# sheet1.net
KiCad netlist of a schematic drawn in Altium Designer
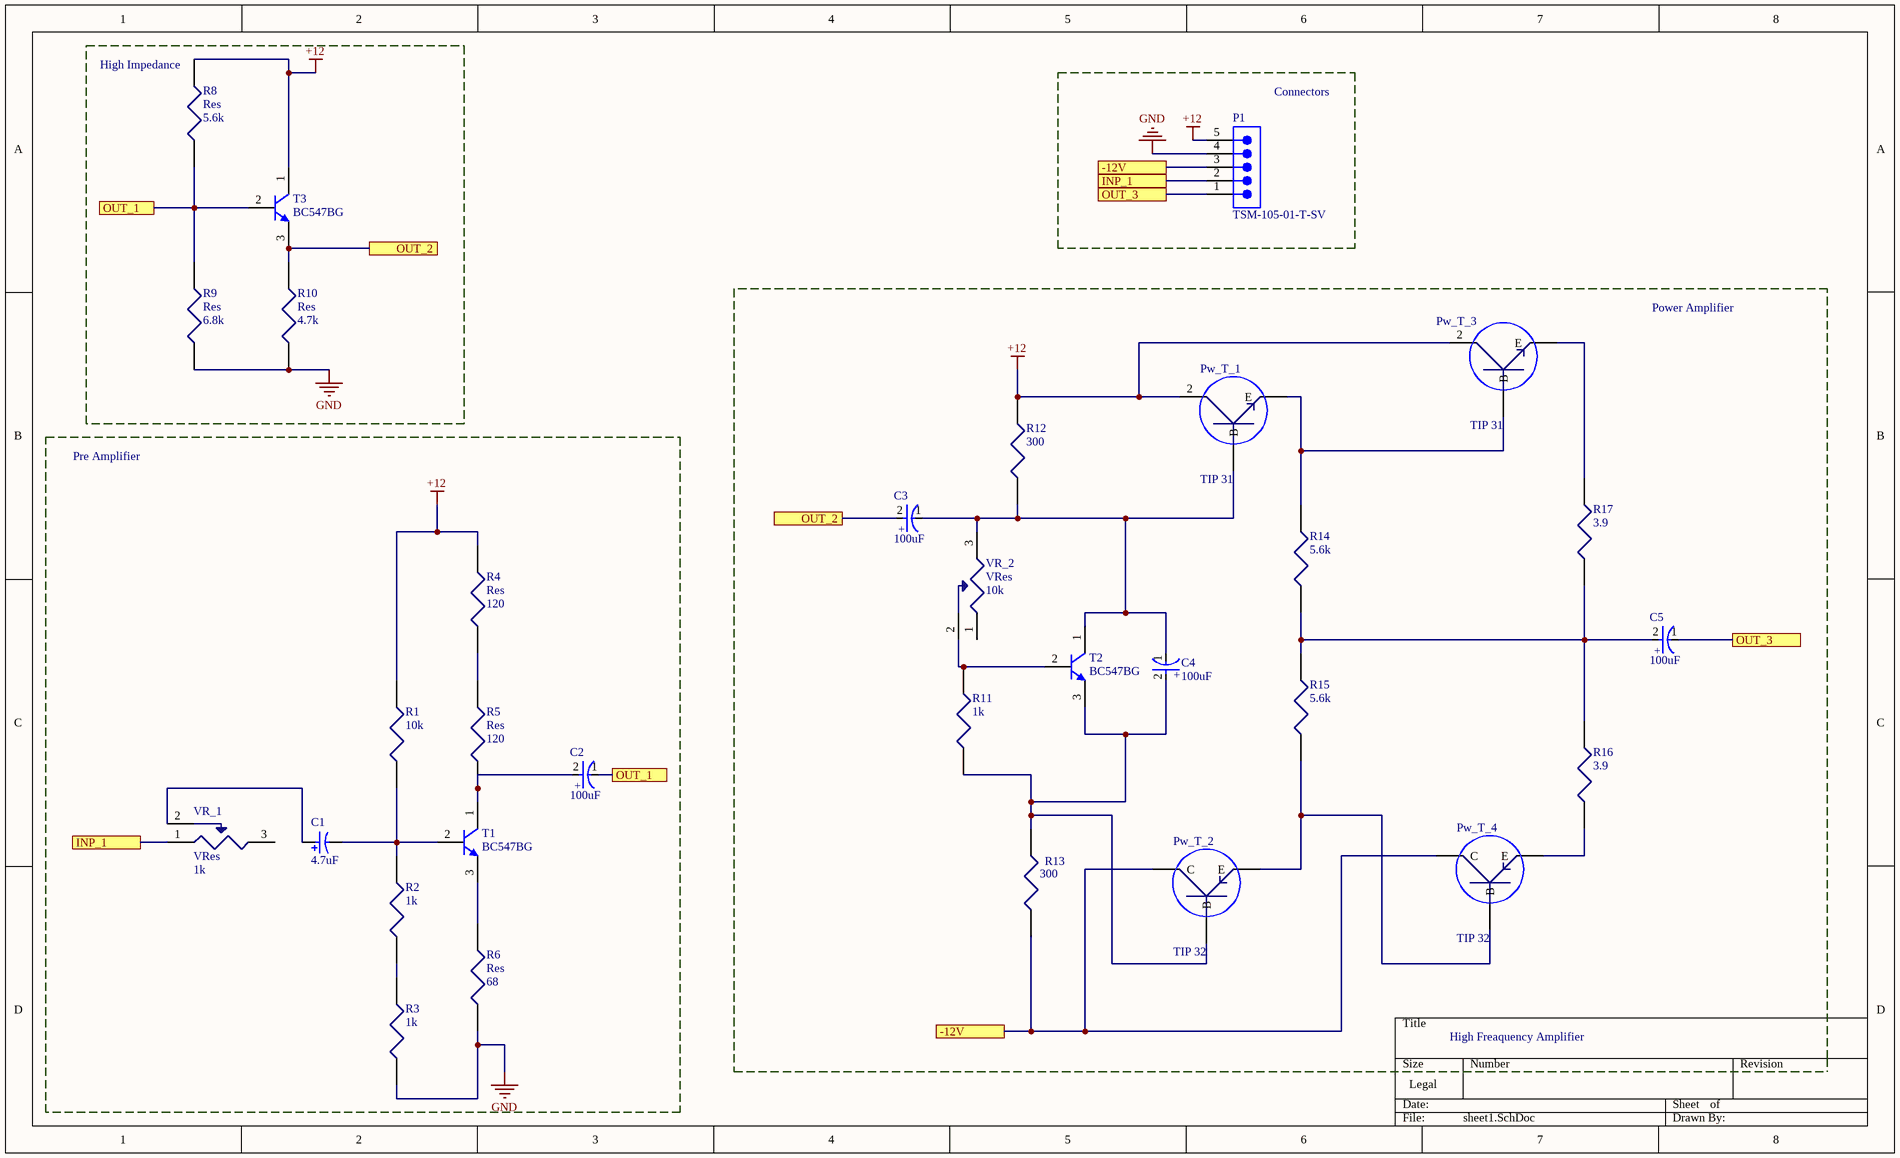
[diagram p0: sheet1.SchDoc]

(export (version "E")
  (design (tool "Eeschema 10.0.6"))
  (components
    (comp (ref "C1")
      (value "4.7uF")
      (footprint "CAPPR55-200-1100X500X1200")
      (description "Aluminum Electrolytic Capacitor, 4.7 uF, +/- 20%, 50 V, -40 to 85 degC, 2-Pin THD, RoHS, Bulk")
      (fields (field (name "VOLTAGE") "50V") (field (name "MANUFACTURER") "Panasonic"))
      (libsource (lib "Altium Content Vault") (part "CAP-P-2"))
    )
    (comp (ref "C2")
      (value "100uF")
      (footprint "FP-EEU-FR1H101B-MFG")
      (description "CAP ALUM 100UF 20% 50V RADIAL")
      (fields (field (name "TOLERANCE") "20%"))
      (libsource (lib "Altium Content Vault") (part "cf48714ba7e38822c1575c7ec0b6d1f"))
    )
    (comp (ref "C3")
      (value "100uF")
      (footprint "FP-EEU-FR1H101B-MFG")
      (description "CAP ALUM 100UF 20% 50V RADIAL")
      (fields (field (name "TOLERANCE") "20%"))
      (libsource (lib "Altium Content Vault") (part "cf48714ba7e38822c1575c7ec0b6d1f"))
    )
    (comp (ref "C4")
      (value "100uF")
      (footprint "FP-EEU-FR1H101B-MFG")
      (description "CAP ALUM 100UF 20% 50V RADIAL")
      (fields (field (name "TOLERANCE") "20%"))
      (libsource (lib "Altium Content Vault") (part "cf48714ba7e38822c1575c7ec0b6d1f"))
    )
    (comp (ref "C5")
      (value "100uF")
      (footprint "FP-EEU-FR1H101B-MFG")
      (description "CAP ALUM 100UF 20% 50V RADIAL")
      (fields (field (name "TOLERANCE") "20%"))
      (libsource (lib "Altium Content Vault") (part "cf48714ba7e38822c1575c7ec0b6d1f"))
    )
    (comp (ref "P1")
      (value "TSM-105-01-T-SV")
      (footprint "SMTC-TSM-105-01-X-SV")
      (description "0.025\" SQ Post Header, Surface Mount, Vertical, -55 to 105 degC, 2.54 mm Pitch, 5-Pin, Male, RoHS")
      (fields (field (name "MANUFACTURER") "Samtec"))
      (libsource (lib "Altium Content Vault") (part "SMTC-TSM-105-01-X-SV"))
    )
    (comp (ref "Pw_T_1") (value "TIP 31") (footprint "TIP 31") (libsource (lib "Funcgen") (part "TIP 31")))
    (comp (ref "Pw_T_2") (value "TIP 32") (footprint "TIP 31") (libsource (lib "Funcgen") (part "TIP 32")))
    (comp (ref "Pw_T_3") (value "TIP 31") (footprint "TIP 31") (libsource (lib "Funcgen") (part "TIP 31")))
    (comp (ref "Pw_T_4") (value "TIP 32") (footprint "TIP 31") (libsource (lib "Funcgen") (part "TIP 32")))
    (comp (ref "R1") (value "10k") (footprint "Res") (libsource (lib "Funcgen") (part "Res")))
    (comp (ref "R2") (value "1k") (footprint "Res") (libsource (lib "Funcgen") (part "Res")))
    (comp (ref "R3") (value "1k") (footprint "Res") (libsource (lib "Funcgen") (part "Res")))
    (comp (ref "R4")
      (value "Res")
      (footprint "Res")
      (fields (field (name "ALTIUM_VALUE") "120"))
      (libsource (lib "Funcgen") (part "Res"))
    )
    (comp (ref "R5")
      (value "Res")
      (footprint "Res")
      (fields (field (name "ALTIUM_VALUE") "120"))
      (libsource (lib "Funcgen") (part "Res"))
    )
    (comp (ref "R6")
      (value "Res")
      (footprint "Res")
      (fields (field (name "ALTIUM_VALUE") "68"))
      (libsource (lib "Funcgen") (part "Res"))
    )
    (comp (ref "R8")
      (value "Res")
      (footprint "Res")
      (fields (field (name "ALTIUM_VALUE") "5.6k"))
      (libsource (lib "Funcgen") (part "Res"))
    )
    (comp (ref "R9")
      (value "Res")
      (footprint "Res")
      (fields (field (name "ALTIUM_VALUE") "6.8k"))
      (libsource (lib "Funcgen") (part "Res"))
    )
    (comp (ref "R10")
      (value "Res")
      (footprint "Res")
      (fields (field (name "ALTIUM_VALUE") "4.7k"))
      (libsource (lib "Funcgen") (part "Res"))
    )
    (comp (ref "R11") (value "1k") (footprint "Res") (libsource (lib "Funcgen") (part "Res")))
    (comp (ref "R12") (value "300") (footprint "Res") (libsource (lib "Funcgen") (part "Res")))
    (comp (ref "R13") (value "300") (footprint "Res") (libsource (lib "Funcgen") (part "Res")))
    (comp (ref "R14") (value "5.6k") (footprint "Res") (libsource (lib "Funcgen") (part "Res")))
    (comp (ref "R15") (value "5.6k") (footprint "Res") (libsource (lib "Funcgen") (part "Res")))
    (comp (ref "R16") (value "3.9") (footprint "Res") (libsource (lib "Funcgen") (part "Res")))
    (comp (ref "R17") (value "3.9") (footprint "Res") (libsource (lib "Funcgen") (part "Res")))
    (comp (ref "T1")
      (value "BC547BG")
      (footprint "ONSC-TO-92-3-29-11")
      (description "Amplifier Transistor, NPN Silicon, 3-Pin TO-92, Pb-Free, Bulk Box")
      (fields (field (name "MANUFACTURER") "On Semiconductor"))
      (libsource (lib "Altium Content Vault") (part "ONSC-NPN-C1B2E3-3"))
    )
    (comp (ref "T2")
      (value "BC547BG")
      (footprint "ONSC-TO-92-3-29-11")
      (description "Amplifier Transistor, NPN Silicon, 3-Pin TO-92, Pb-Free, Bulk Box")
      (fields (field (name "MANUFACTURER") "On Semiconductor"))
      (libsource (lib "Altium Content Vault") (part "ONSC-NPN-C1B2E3-3"))
    )
    (comp (ref "T3")
      (value "BC547BG")
      (footprint "ONSC-TO-92-3-29-11")
      (description "Amplifier Transistor, NPN Silicon, 3-Pin TO-92, Pb-Free, Bulk Box")
      (fields (field (name "MANUFACTURER") "On Semiconductor"))
      (libsource (lib "Altium Content Vault") (part "ONSC-NPN-C1B2E3-3"))
    )
    (comp (ref "VR_1")
      (value "VRes")
      (footprint "VerRes")
      (fields (field (name "ALTIUM_VALUE") "1k"))
      (libsource (lib "Funcgen") (part "VRes"))
    )
    (comp (ref "VR_2")
      (value "VRes")
      (footprint "VerRes")
      (fields (field (name "ALTIUM_VALUE") "10k"))
      (libsource (lib "Funcgen") (part "VRes"))
    )
  )
  (nets
    (net (code "1") (name "+12") (class "Default")
      (node (ref "P1") (pin "5") (pinfunction "5_5") (pintype "passive"))
      (node (ref "Pw_T_1") (pin "2") (pinfunction "3_2") (pintype "passive"))
      (node (ref "Pw_T_3") (pin "2") (pinfunction "3_2") (pintype "passive"))
      (node (ref "R1") (pin "2") (pinfunction "2_2") (pintype "passive"))
      (node (ref "R12") (pin "2") (pinfunction "2_2") (pintype "passive"))
      (node (ref "R4") (pin "2") (pinfunction "2_2") (pintype "passive"))
      (node (ref "R8") (pin "2") (pinfunction "2_2") (pintype "passive"))
      (node (ref "T3") (pin "1") (pinfunction "C_1") (pintype "passive"))
    )
    (net (code "2") (name "/-12V") (class "Default")
      (node (ref "P1") (pin "3") (pinfunction "3_3") (pintype "passive"))
      (node (ref "Pw_T_2") (pin "2") (pinfunction "C_2") (pintype "passive"))
      (node (ref "Pw_T_4") (pin "2") (pinfunction "C_2") (pintype "passive"))
      (node (ref "R13") (pin "1") (pinfunction "1_1") (pintype "passive"))
    )
    (net (code "3") (name "/INP_1") (class "Default")
      (node (ref "P1") (pin "2") (pinfunction "2_2") (pintype "passive"))
      (node (ref "VR_1") (pin "1") (pinfunction "1_1") (pintype "passive"))
    )
    (net (code "4") (name "/OUT_1") (class "Default")
      (node (ref "C2") (pin "1") (pinfunction "C_1") (pintype "passive"))
      (node (ref "R8") (pin "1") (pinfunction "1_1") (pintype "passive"))
      (node (ref "R9") (pin "2") (pinfunction "2_2") (pintype "passive"))
      (node (ref "T3") (pin "2") (pinfunction "B_2") (pintype "passive"))
    )
    (net (code "5") (name "/OUT_2") (class "Default")
      (node (ref "C3") (pin "2") (pinfunction "A_2") (pintype "passive"))
      (node (ref "R10") (pin "2") (pinfunction "2_2") (pintype "passive"))
      (node (ref "T3") (pin "3") (pinfunction "E_3") (pintype "passive"))
    )
    (net (code "6") (name "/OUT_3") (class "Default")
      (node (ref "C5") (pin "1") (pinfunction "C_1") (pintype "passive"))
      (node (ref "P1") (pin "1") (pinfunction "1_1") (pintype "passive"))
    )
    (net (code "7") (name "GND") (class "Default")
      (node (ref "P1") (pin "4") (pinfunction "4_4") (pintype "passive"))
      (node (ref "R10") (pin "1") (pinfunction "1_1") (pintype "passive"))
      (node (ref "R3") (pin "1") (pinfunction "1_1") (pintype "passive"))
      (node (ref "R6") (pin "1") (pinfunction "1_1") (pintype "passive"))
      (node (ref "R9") (pin "1") (pinfunction "1_1") (pintype "passive"))
    )
    (net (code "8") (name "Net-(C1-Pad1)") (class "Default")
      (node (ref "C1") (pin "1") (pinfunction "1_1") (pintype "passive"))
      (node (ref "VR_1") (pin "2") (pinfunction "2_2") (pintype "passive"))
    )
    (net (code "9") (name "Net-(C2-A)") (class "Default")
      (node (ref "C2") (pin "2") (pinfunction "A_2") (pintype "passive"))
      (node (ref "R5") (pin "1") (pinfunction "1_1") (pintype "passive"))
      (node (ref "T1") (pin "1") (pinfunction "C_1") (pintype "passive"))
    )
    (net (code "10") (name "Net-(C3-C)") (class "Default")
      (node (ref "C3") (pin "1") (pinfunction "C_1") (pintype "passive"))
      (node (ref "C4") (pin "1") (pinfunction "C_1") (pintype "passive"))
      (node (ref "Pw_T_1") (pin "1") (pinfunction "B_1") (pintype "passive"))
      (node (ref "R12") (pin "1") (pinfunction "1_1") (pintype "passive"))
      (node (ref "T2") (pin "1") (pinfunction "C_1") (pintype "passive"))
      (node (ref "VR_2") (pin "3") (pinfunction "3_3") (pintype "passive"))
    )
    (net (code "11") (name "Net-(C4-A)") (class "Default")
      (node (ref "C4") (pin "2") (pinfunction "A_2") (pintype "passive"))
      (node (ref "Pw_T_2") (pin "1") (pinfunction "B_1") (pintype "passive"))
      (node (ref "R11") (pin "1") (pinfunction "1_1") (pintype "passive"))
      (node (ref "R13") (pin "2") (pinfunction "2_2") (pintype "passive"))
      (node (ref "T2") (pin "3") (pinfunction "E_3") (pintype "passive"))
    )
    (net (code "12") (name "Net-(C5-A)") (class "Default")
      (node (ref "C5") (pin "2") (pinfunction "A_2") (pintype "passive"))
      (node (ref "R14") (pin "1") (pinfunction "1_1") (pintype "passive"))
      (node (ref "R15") (pin "2") (pinfunction "2_2") (pintype "passive"))
      (node (ref "R16") (pin "2") (pinfunction "2_2") (pintype "passive"))
      (node (ref "R17") (pin "1") (pinfunction "1_1") (pintype "passive"))
    )
    (net (code "13") (name "Net-(Pw_T_1-E)") (class "Default")
      (node (ref "Pw_T_1") (pin "3") (pinfunction "E_3") (pintype "passive"))
      (node (ref "Pw_T_3") (pin "1") (pinfunction "B_1") (pintype "passive"))
      (node (ref "R14") (pin "2") (pinfunction "2_2") (pintype "passive"))
    )
    (net (code "14") (name "Net-(Pw_T_2-E)") (class "Default")
      (node (ref "Pw_T_2") (pin "3") (pinfunction "E_3") (pintype "passive"))
      (node (ref "Pw_T_4") (pin "1") (pinfunction "B_1") (pintype "passive"))
      (node (ref "R15") (pin "1") (pinfunction "1_1") (pintype "passive"))
    )
    (net (code "15") (name "Net-(Pw_T_3-E)") (class "Default")
      (node (ref "Pw_T_3") (pin "3") (pinfunction "E_3") (pintype "passive"))
      (node (ref "R17") (pin "2") (pinfunction "2_2") (pintype "passive"))
    )
    (net (code "16") (name "Net-(Pw_T_4-E)") (class "Default")
      (node (ref "Pw_T_4") (pin "3") (pinfunction "E_3") (pintype "passive"))
      (node (ref "R16") (pin "1") (pinfunction "1_1") (pintype "passive"))
    )
    (net (code "17") (name "Net-(R2-Pad1)") (class "Default")
      (node (ref "R2") (pin "1") (pinfunction "1_1") (pintype "passive"))
      (node (ref "R3") (pin "2") (pinfunction "2_2") (pintype "passive"))
    )
    (net (code "18") (name "Net-(R4-Pad1)") (class "Default")
      (node (ref "R4") (pin "1") (pinfunction "1_1") (pintype "passive"))
      (node (ref "R5") (pin "2") (pinfunction "2_2") (pintype "passive"))
    )
    (net (code "19") (name "Net-(T1-B)") (class "Default")
      (node (ref "C1") (pin "2") (pinfunction "2_2") (pintype "passive"))
      (node (ref "R1") (pin "1") (pinfunction "1_1") (pintype "passive"))
      (node (ref "R2") (pin "2") (pinfunction "2_2") (pintype "passive"))
      (node (ref "T1") (pin "2") (pinfunction "B_2") (pintype "passive"))
    )
    (net (code "20") (name "Net-(T1-E)") (class "Default")
      (node (ref "R6") (pin "2") (pinfunction "2_2") (pintype "passive"))
      (node (ref "T1") (pin "3") (pinfunction "E_3") (pintype "passive"))
    )
    (net (code "21") (name "Net-(T2-B)") (class "Default")
      (node (ref "R11") (pin "2") (pinfunction "2_2") (pintype "passive"))
      (node (ref "T2") (pin "2") (pinfunction "B_2") (pintype "passive"))
      (node (ref "VR_2") (pin "2") (pinfunction "2_2") (pintype "passive"))
    )
    (net (code "22") (name "unconnected-(VR_1-Pad3)") (class "Default")
      (node (ref "VR_1") (pin "3") (pinfunction "3_3") (pintype "passive"))
    )
    (net (code "23") (name "unconnected-(VR_2-Pad1)") (class "Default")
      (node (ref "VR_2") (pin "1") (pinfunction "1_1") (pintype "passive"))
    )
  )
)
